# LED_CUBE_595.net
KiCad netlist of a schematic drawn in EAGLE
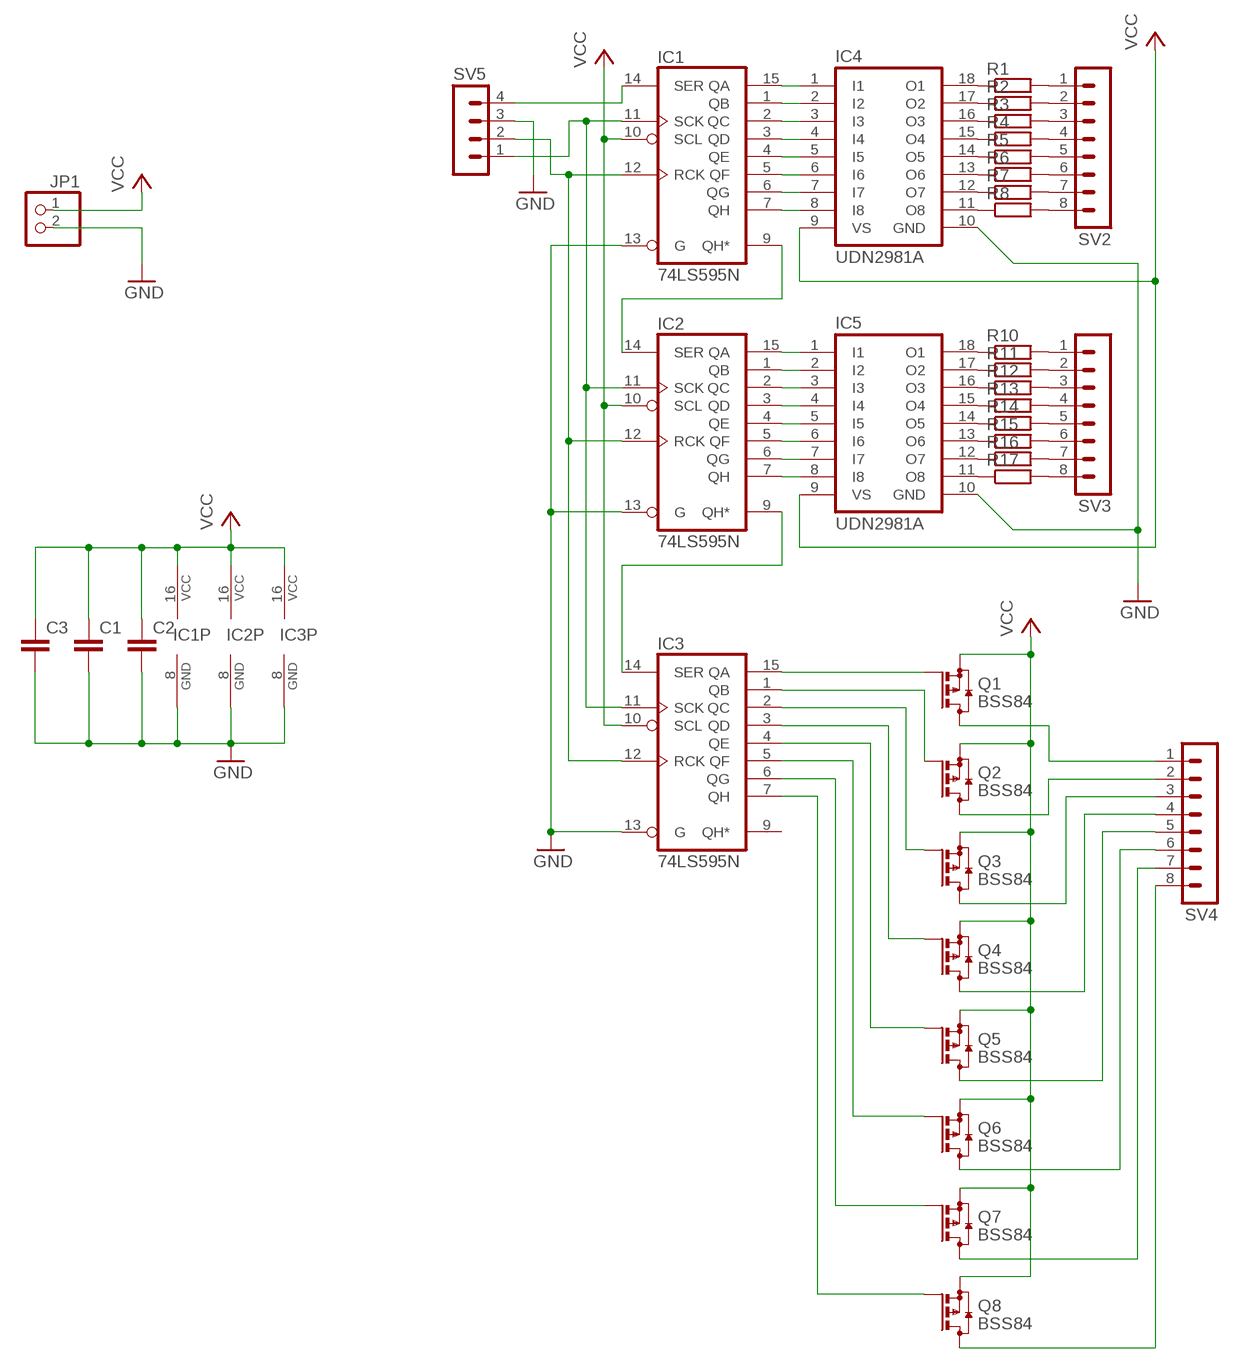
[diagram p0: schematic, sheet 1]

(export (version "E")
  (design (tool "Eeschema 10.0.6"))
  (components
    (comp (ref "C1")
      (value "C-EU025-025X050")
      (footprint "eagle-import:C025-025X050")
      (libsource (lib "eagle-import") (part "C-EU025-025X050"))
    )
    (comp (ref "C2")
      (value "C-EU025-025X050")
      (footprint "eagle-import:C025-025X050")
      (libsource (lib "eagle-import") (part "C-EU025-025X050"))
    )
    (comp (ref "C3")
      (value "C-EU025-025X050")
      (footprint "eagle-import:C025-025X050")
      (libsource (lib "eagle-import") (part "C-EU025-025X050"))
    )
    (comp (ref "IC1")
      (value "74LS595N")
      (footprint "eagle-import:DIL16")
      (libsource (lib "eagle-import") (part "74595NLS"))
    )
    (comp (ref "IC2")
      (value "74LS595N")
      (footprint "eagle-import:DIL16")
      (libsource (lib "eagle-import") (part "74595NLS"))
    )
    (comp (ref "IC3")
      (value "74LS595N")
      (footprint "eagle-import:DIL16")
      (libsource (lib "eagle-import") (part "74595NLS"))
    )
    (comp (ref "IC4")
      (value "UDN2981A")
      (footprint "eagle-import:DIL18")
      (libsource (lib "eagle-import") (part "UDN298A1"))
    )
    (comp (ref "IC5")
      (value "UDN2981A")
      (footprint "eagle-import:DIL18")
      (libsource (lib "eagle-import") (part "UDN298A1"))
    )
    (comp (ref "JP1")
      (value "PINHD-1X2")
      (footprint "eagle-import:1X02")
      (libsource (lib "eagle-import") (part "PINHD-1X2"))
    )
    (comp (ref "Q1")
      (value "BSS84")
      (footprint "eagle-import:SOT23")
      (libsource (lib "eagle-import") (part "BSS84"))
    )
    (comp (ref "Q2")
      (value "BSS84")
      (footprint "eagle-import:SOT23")
      (libsource (lib "eagle-import") (part "BSS84"))
    )
    (comp (ref "Q3")
      (value "BSS84")
      (footprint "eagle-import:SOT23")
      (libsource (lib "eagle-import") (part "BSS84"))
    )
    (comp (ref "Q4")
      (value "BSS84")
      (footprint "eagle-import:SOT23")
      (libsource (lib "eagle-import") (part "BSS84"))
    )
    (comp (ref "Q5")
      (value "BSS84")
      (footprint "eagle-import:SOT23")
      (libsource (lib "eagle-import") (part "BSS84"))
    )
    (comp (ref "Q6")
      (value "BSS84")
      (footprint "eagle-import:SOT23")
      (libsource (lib "eagle-import") (part "BSS84"))
    )
    (comp (ref "Q7")
      (value "BSS84")
      (footprint "eagle-import:SOT23")
      (libsource (lib "eagle-import") (part "BSS84"))
    )
    (comp (ref "Q8")
      (value "BSS84")
      (footprint "eagle-import:SOT23")
      (libsource (lib "eagle-import") (part "BSS84"))
    )
    (comp (ref "R1")
      (value "R-EU_0204/2V")
      (footprint "eagle-import:0204V")
      (libsource (lib "eagle-import") (part "R-EU_0204/2V"))
    )
    (comp (ref "R2")
      (value "R-EU_0204/2V")
      (footprint "eagle-import:0204V")
      (libsource (lib "eagle-import") (part "R-EU_0204/2V"))
    )
    (comp (ref "R3")
      (value "R-EU_0204/2V")
      (footprint "eagle-import:0204V")
      (libsource (lib "eagle-import") (part "R-EU_0204/2V"))
    )
    (comp (ref "R4")
      (value "R-EU_0204/2V")
      (footprint "eagle-import:0204V")
      (libsource (lib "eagle-import") (part "R-EU_0204/2V"))
    )
    (comp (ref "R5")
      (value "R-EU_0204/2V")
      (footprint "eagle-import:0204V")
      (libsource (lib "eagle-import") (part "R-EU_0204/2V"))
    )
    (comp (ref "R6")
      (value "R-EU_0204/2V")
      (footprint "eagle-import:0204V")
      (libsource (lib "eagle-import") (part "R-EU_0204/2V"))
    )
    (comp (ref "R7")
      (value "R-EU_0204/2V")
      (footprint "eagle-import:0204V")
      (libsource (lib "eagle-import") (part "R-EU_0204/2V"))
    )
    (comp (ref "R8")
      (value "R-EU_0204/2V")
      (footprint "eagle-import:0204V")
      (libsource (lib "eagle-import") (part "R-EU_0204/2V"))
    )
    (comp (ref "R10")
      (value "R-EU_0204/2V")
      (footprint "eagle-import:0204V")
      (libsource (lib "eagle-import") (part "R-EU_0204/2V"))
    )
    (comp (ref "R11")
      (value "R-EU_0204/2V")
      (footprint "eagle-import:0204V")
      (libsource (lib "eagle-import") (part "R-EU_0204/2V"))
    )
    (comp (ref "R12")
      (value "R-EU_0204/2V")
      (footprint "eagle-import:0204V")
      (libsource (lib "eagle-import") (part "R-EU_0204/2V"))
    )
    (comp (ref "R13")
      (value "R-EU_0204/2V")
      (footprint "eagle-import:0204V")
      (libsource (lib "eagle-import") (part "R-EU_0204/2V"))
    )
    (comp (ref "R14")
      (value "R-EU_0204/2V")
      (footprint "eagle-import:0204V")
      (libsource (lib "eagle-import") (part "R-EU_0204/2V"))
    )
    (comp (ref "R15")
      (value "R-EU_0204/2V")
      (footprint "eagle-import:0204V")
      (libsource (lib "eagle-import") (part "R-EU_0204/2V"))
    )
    (comp (ref "R16")
      (value "R-EU_0204/2V")
      (footprint "eagle-import:0204V")
      (libsource (lib "eagle-import") (part "R-EU_0204/2V"))
    )
    (comp (ref "R17")
      (value "R-EU_0204/2V")
      (footprint "eagle-import:0204V")
      (libsource (lib "eagle-import") (part "R-EU_0204/2V"))
    )
    (comp (ref "SV2")
      (value "MA08-1")
      (footprint "eagle-import:MA08-1")
      (libsource (lib "eagle-import") (part "MA08-1"))
    )
    (comp (ref "SV3")
      (value "MA08-1")
      (footprint "eagle-import:MA08-1")
      (libsource (lib "eagle-import") (part "MA08-1"))
    )
    (comp (ref "SV4")
      (value "MA08-1")
      (footprint "eagle-import:MA08-1")
      (libsource (lib "eagle-import") (part "MA08-1"))
    )
    (comp (ref "SV5")
      (value "MA04-1")
      (footprint "eagle-import:MA04-1")
      (libsource (lib "eagle-import") (part "MA04-1"))
    )
  )
  (nets
    (net (code "1") (name "GND") (class "Default")
      (node (ref "C1") (pin "2") (pinfunction "2_2") (pintype "passive"))
      (node (ref "C2") (pin "2") (pinfunction "2_2") (pintype "passive"))
      (node (ref "C3") (pin "2") (pinfunction "2_2") (pintype "passive"))
      (node (ref "IC1") (pin "13") (pinfunction "G_13") (pintype "input"))
      (node (ref "IC1") (pin "8") (pinfunction "GND_8") (pintype "power_in"))
      (node (ref "IC2") (pin "13") (pinfunction "G_13") (pintype "input"))
      (node (ref "IC2") (pin "8") (pinfunction "GND_8") (pintype "power_in"))
      (node (ref "IC3") (pin "13") (pinfunction "G_13") (pintype "input"))
      (node (ref "IC3") (pin "8") (pinfunction "GND_8") (pintype "power_in"))
      (node (ref "IC4") (pin "10") (pinfunction "GND_10") (pintype "power_in"))
      (node (ref "IC5") (pin "10") (pinfunction "GND_10") (pintype "power_in"))
      (node (ref "JP1") (pin "2") (pinfunction "2_2") (pintype "passive"))
      (node (ref "SV5") (pin "3") (pinfunction "3_3") (pintype "passive"))
    )
    (net (code "2") (name "Net-(IC1A-QA)") (class "Default")
      (node (ref "IC1") (pin "15") (pinfunction "QA_15") (pintype "tri_state"))
      (node (ref "IC4") (pin "1") (pinfunction "I1_1") (pintype "input"))
    )
    (net (code "3") (name "Net-(IC1A-QB)") (class "Default")
      (node (ref "IC1") (pin "1") (pinfunction "QB_1") (pintype "tri_state"))
      (node (ref "IC4") (pin "2") (pinfunction "I2_2") (pintype "input"))
    )
    (net (code "4") (name "Net-(IC1A-QC)") (class "Default")
      (node (ref "IC1") (pin "2") (pinfunction "QC_2") (pintype "tri_state"))
      (node (ref "IC4") (pin "3") (pinfunction "I3_3") (pintype "input"))
    )
    (net (code "5") (name "Net-(IC1A-QD)") (class "Default")
      (node (ref "IC1") (pin "3") (pinfunction "QD_3") (pintype "tri_state"))
      (node (ref "IC4") (pin "4") (pinfunction "I4_4") (pintype "input"))
    )
    (net (code "6") (name "Net-(IC1A-QE)") (class "Default")
      (node (ref "IC1") (pin "4") (pinfunction "QE_4") (pintype "tri_state"))
      (node (ref "IC4") (pin "5") (pinfunction "I5_5") (pintype "input"))
    )
    (net (code "7") (name "Net-(IC1A-QF)") (class "Default")
      (node (ref "IC1") (pin "5") (pinfunction "QF_5") (pintype "tri_state"))
      (node (ref "IC4") (pin "6") (pinfunction "I6_6") (pintype "input"))
    )
    (net (code "8") (name "Net-(IC1A-QG)") (class "Default")
      (node (ref "IC1") (pin "6") (pinfunction "QG_6") (pintype "tri_state"))
      (node (ref "IC4") (pin "7") (pinfunction "I7_7") (pintype "input"))
    )
    (net (code "9") (name "Net-(IC1A-QH)") (class "Default")
      (node (ref "IC1") (pin "7") (pinfunction "QH_7") (pintype "tri_state"))
      (node (ref "IC4") (pin "8") (pinfunction "I8_8") (pintype "input"))
    )
    (net (code "10") (name "Net-(IC1A-QH*)") (class "Default")
      (node (ref "IC1") (pin "9") (pinfunction "QH*_9") (pintype "tri_state"))
      (node (ref "IC2") (pin "14") (pinfunction "SER_14") (pintype "input"))
    )
    (net (code "11") (name "Net-(IC1A-RCK)") (class "Default")
      (node (ref "IC1") (pin "12") (pinfunction "RCK_12") (pintype "input"))
      (node (ref "IC2") (pin "12") (pinfunction "RCK_12") (pintype "input"))
      (node (ref "IC3") (pin "12") (pinfunction "RCK_12") (pintype "input"))
      (node (ref "SV5") (pin "2") (pinfunction "2_2") (pintype "passive"))
    )
    (net (code "12") (name "Net-(IC1A-SCK)") (class "Default")
      (node (ref "IC1") (pin "11") (pinfunction "SCK_11") (pintype "input"))
      (node (ref "IC2") (pin "11") (pinfunction "SCK_11") (pintype "input"))
      (node (ref "IC3") (pin "11") (pinfunction "SCK_11") (pintype "input"))
      (node (ref "SV5") (pin "1") (pinfunction "1_1") (pintype "passive"))
    )
    (net (code "13") (name "Net-(IC1A-SER)") (class "Default")
      (node (ref "IC1") (pin "14") (pinfunction "SER_14") (pintype "input"))
      (node (ref "SV5") (pin "4") (pinfunction "4_4") (pintype "passive"))
    )
    (net (code "14") (name "Net-(IC2A-QA)") (class "Default")
      (node (ref "IC2") (pin "15") (pinfunction "QA_15") (pintype "tri_state"))
      (node (ref "IC5") (pin "1") (pinfunction "I1_1") (pintype "input"))
    )
    (net (code "15") (name "Net-(IC2A-QB)") (class "Default")
      (node (ref "IC2") (pin "1") (pinfunction "QB_1") (pintype "tri_state"))
      (node (ref "IC5") (pin "2") (pinfunction "I2_2") (pintype "input"))
    )
    (net (code "16") (name "Net-(IC2A-QC)") (class "Default")
      (node (ref "IC2") (pin "2") (pinfunction "QC_2") (pintype "tri_state"))
      (node (ref "IC5") (pin "3") (pinfunction "I3_3") (pintype "input"))
    )
    (net (code "17") (name "Net-(IC2A-QD)") (class "Default")
      (node (ref "IC2") (pin "3") (pinfunction "QD_3") (pintype "tri_state"))
      (node (ref "IC5") (pin "4") (pinfunction "I4_4") (pintype "input"))
    )
    (net (code "18") (name "Net-(IC2A-QE)") (class "Default")
      (node (ref "IC2") (pin "4") (pinfunction "QE_4") (pintype "tri_state"))
      (node (ref "IC5") (pin "5") (pinfunction "I5_5") (pintype "input"))
    )
    (net (code "19") (name "Net-(IC2A-QF)") (class "Default")
      (node (ref "IC2") (pin "5") (pinfunction "QF_5") (pintype "tri_state"))
      (node (ref "IC5") (pin "6") (pinfunction "I6_6") (pintype "input"))
    )
    (net (code "20") (name "Net-(IC2A-QG)") (class "Default")
      (node (ref "IC2") (pin "6") (pinfunction "QG_6") (pintype "tri_state"))
      (node (ref "IC5") (pin "7") (pinfunction "I7_7") (pintype "input"))
    )
    (net (code "21") (name "Net-(IC2A-QH)") (class "Default")
      (node (ref "IC2") (pin "7") (pinfunction "QH_7") (pintype "tri_state"))
      (node (ref "IC5") (pin "8") (pinfunction "I8_8") (pintype "input"))
    )
    (net (code "22") (name "Net-(IC2A-QH*)") (class "Default")
      (node (ref "IC2") (pin "9") (pinfunction "QH*_9") (pintype "tri_state"))
      (node (ref "IC3") (pin "14") (pinfunction "SER_14") (pintype "input"))
    )
    (net (code "23") (name "Net-(IC3A-QA)") (class "Default")
      (node (ref "IC3") (pin "15") (pinfunction "QA_15") (pintype "tri_state"))
      (node (ref "Q1") (pin "1") (pinfunction "G_1") (pintype "passive"))
    )
    (net (code "24") (name "Net-(IC3A-QB)") (class "Default")
      (node (ref "IC3") (pin "1") (pinfunction "QB_1") (pintype "tri_state"))
      (node (ref "Q2") (pin "1") (pinfunction "G_1") (pintype "passive"))
    )
    (net (code "25") (name "Net-(IC3A-QC)") (class "Default")
      (node (ref "IC3") (pin "2") (pinfunction "QC_2") (pintype "tri_state"))
      (node (ref "Q3") (pin "1") (pinfunction "G_1") (pintype "passive"))
    )
    (net (code "26") (name "Net-(IC3A-QD)") (class "Default")
      (node (ref "IC3") (pin "3") (pinfunction "QD_3") (pintype "tri_state"))
      (node (ref "Q4") (pin "1") (pinfunction "G_1") (pintype "passive"))
    )
    (net (code "27") (name "Net-(IC3A-QE)") (class "Default")
      (node (ref "IC3") (pin "4") (pinfunction "QE_4") (pintype "tri_state"))
      (node (ref "Q5") (pin "1") (pinfunction "G_1") (pintype "passive"))
    )
    (net (code "28") (name "Net-(IC3A-QF)") (class "Default")
      (node (ref "IC3") (pin "5") (pinfunction "QF_5") (pintype "tri_state"))
      (node (ref "Q6") (pin "1") (pinfunction "G_1") (pintype "passive"))
    )
    (net (code "29") (name "Net-(IC3A-QG)") (class "Default")
      (node (ref "IC3") (pin "6") (pinfunction "QG_6") (pintype "tri_state"))
      (node (ref "Q7") (pin "1") (pinfunction "G_1") (pintype "passive"))
    )
    (net (code "30") (name "Net-(IC3A-QH)") (class "Default")
      (node (ref "IC3") (pin "7") (pinfunction "QH_7") (pintype "tri_state"))
      (node (ref "Q8") (pin "1") (pinfunction "G_1") (pintype "passive"))
    )
    (net (code "31") (name "Net-(IC4-O1)") (class "Default")
      (node (ref "IC4") (pin "18") (pinfunction "O1_18") (pintype "open_collector"))
      (node (ref "R1") (pin "1") (pinfunction "1_1") (pintype "passive"))
    )
    (net (code "32") (name "Net-(IC4-O2)") (class "Default")
      (node (ref "IC4") (pin "17") (pinfunction "O2_17") (pintype "open_collector"))
      (node (ref "R2") (pin "1") (pinfunction "1_1") (pintype "passive"))
    )
    (net (code "33") (name "Net-(IC4-O3)") (class "Default")
      (node (ref "IC4") (pin "16") (pinfunction "O3_16") (pintype "open_collector"))
      (node (ref "R3") (pin "1") (pinfunction "1_1") (pintype "passive"))
    )
    (net (code "34") (name "Net-(IC4-O4)") (class "Default")
      (node (ref "IC4") (pin "15") (pinfunction "O4_15") (pintype "open_collector"))
      (node (ref "R4") (pin "1") (pinfunction "1_1") (pintype "passive"))
    )
    (net (code "35") (name "Net-(IC4-O5)") (class "Default")
      (node (ref "IC4") (pin "14") (pinfunction "O5_14") (pintype "open_collector"))
      (node (ref "R5") (pin "1") (pinfunction "1_1") (pintype "passive"))
    )
    (net (code "36") (name "Net-(IC4-O6)") (class "Default")
      (node (ref "IC4") (pin "13") (pinfunction "O6_13") (pintype "open_collector"))
      (node (ref "R6") (pin "1") (pinfunction "1_1") (pintype "passive"))
    )
    (net (code "37") (name "Net-(IC4-O7)") (class "Default")
      (node (ref "IC4") (pin "12") (pinfunction "O7_12") (pintype "open_collector"))
      (node (ref "R7") (pin "1") (pinfunction "1_1") (pintype "passive"))
    )
    (net (code "38") (name "Net-(IC4-O8)") (class "Default")
      (node (ref "IC4") (pin "11") (pinfunction "O8_11") (pintype "open_collector"))
      (node (ref "R8") (pin "1") (pinfunction "1_1") (pintype "passive"))
    )
    (net (code "39") (name "Net-(IC5-O1)") (class "Default")
      (node (ref "IC5") (pin "18") (pinfunction "O1_18") (pintype "open_collector"))
      (node (ref "R10") (pin "1") (pinfunction "1_1") (pintype "passive"))
    )
    (net (code "40") (name "Net-(IC5-O2)") (class "Default")
      (node (ref "IC5") (pin "17") (pinfunction "O2_17") (pintype "open_collector"))
      (node (ref "R11") (pin "1") (pinfunction "1_1") (pintype "passive"))
    )
    (net (code "41") (name "Net-(IC5-O3)") (class "Default")
      (node (ref "IC5") (pin "16") (pinfunction "O3_16") (pintype "open_collector"))
      (node (ref "R12") (pin "1") (pinfunction "1_1") (pintype "passive"))
    )
    (net (code "42") (name "Net-(IC5-O4)") (class "Default")
      (node (ref "IC5") (pin "15") (pinfunction "O4_15") (pintype "open_collector"))
      (node (ref "R13") (pin "1") (pinfunction "1_1") (pintype "passive"))
    )
    (net (code "43") (name "Net-(IC5-O5)") (class "Default")
      (node (ref "IC5") (pin "14") (pinfunction "O5_14") (pintype "open_collector"))
      (node (ref "R14") (pin "1") (pinfunction "1_1") (pintype "passive"))
    )
    (net (code "44") (name "Net-(IC5-O6)") (class "Default")
      (node (ref "IC5") (pin "13") (pinfunction "O6_13") (pintype "open_collector"))
      (node (ref "R15") (pin "1") (pinfunction "1_1") (pintype "passive"))
    )
    (net (code "45") (name "Net-(IC5-O7)") (class "Default")
      (node (ref "IC5") (pin "12") (pinfunction "O7_12") (pintype "open_collector"))
      (node (ref "R16") (pin "1") (pinfunction "1_1") (pintype "passive"))
    )
    (net (code "46") (name "Net-(IC5-O8)") (class "Default")
      (node (ref "IC5") (pin "11") (pinfunction "O8_11") (pintype "open_collector"))
      (node (ref "R17") (pin "1") (pinfunction "1_1") (pintype "passive"))
    )
    (net (code "47") (name "Net-(Q1-D)") (class "Default")
      (node (ref "Q1") (pin "3") (pinfunction "D_3") (pintype "passive"))
      (node (ref "SV4") (pin "1") (pinfunction "1_1") (pintype "passive"))
    )
    (net (code "48") (name "Net-(Q2-D)") (class "Default")
      (node (ref "Q2") (pin "3") (pinfunction "D_3") (pintype "passive"))
      (node (ref "SV4") (pin "2") (pinfunction "2_2") (pintype "passive"))
    )
    (net (code "49") (name "Net-(Q3-D)") (class "Default")
      (node (ref "Q3") (pin "3") (pinfunction "D_3") (pintype "passive"))
      (node (ref "SV4") (pin "3") (pinfunction "3_3") (pintype "passive"))
    )
    (net (code "50") (name "Net-(Q4-D)") (class "Default")
      (node (ref "Q4") (pin "3") (pinfunction "D_3") (pintype "passive"))
      (node (ref "SV4") (pin "4") (pinfunction "4_4") (pintype "passive"))
    )
    (net (code "51") (name "Net-(Q5-D)") (class "Default")
      (node (ref "Q5") (pin "3") (pinfunction "D_3") (pintype "passive"))
      (node (ref "SV4") (pin "5") (pinfunction "5_5") (pintype "passive"))
    )
    (net (code "52") (name "Net-(Q6-D)") (class "Default")
      (node (ref "Q6") (pin "3") (pinfunction "D_3") (pintype "passive"))
      (node (ref "SV4") (pin "6") (pinfunction "6_6") (pintype "passive"))
    )
    (net (code "53") (name "Net-(Q7-D)") (class "Default")
      (node (ref "Q7") (pin "3") (pinfunction "D_3") (pintype "passive"))
      (node (ref "SV4") (pin "7") (pinfunction "7_7") (pintype "passive"))
    )
    (net (code "54") (name "Net-(Q8-D)") (class "Default")
      (node (ref "Q8") (pin "3") (pinfunction "D_3") (pintype "passive"))
      (node (ref "SV4") (pin "8") (pinfunction "8_8") (pintype "passive"))
    )
    (net (code "55") (name "Net-(R1-Pad2)") (class "Default")
      (node (ref "R1") (pin "2") (pinfunction "2_2") (pintype "passive"))
      (node (ref "SV2") (pin "1") (pinfunction "1_1") (pintype "passive"))
    )
    (net (code "56") (name "Net-(R2-Pad2)") (class "Default")
      (node (ref "R2") (pin "2") (pinfunction "2_2") (pintype "passive"))
      (node (ref "SV2") (pin "2") (pinfunction "2_2") (pintype "passive"))
    )
    (net (code "57") (name "Net-(R3-Pad2)") (class "Default")
      (node (ref "R3") (pin "2") (pinfunction "2_2") (pintype "passive"))
      (node (ref "SV2") (pin "3") (pinfunction "3_3") (pintype "passive"))
    )
    (net (code "58") (name "Net-(R4-Pad2)") (class "Default")
      (node (ref "R4") (pin "2") (pinfunction "2_2") (pintype "passive"))
      (node (ref "SV2") (pin "4") (pinfunction "4_4") (pintype "passive"))
    )
    (net (code "59") (name "Net-(R5-Pad2)") (class "Default")
      (node (ref "R5") (pin "2") (pinfunction "2_2") (pintype "passive"))
      (node (ref "SV2") (pin "5") (pinfunction "5_5") (pintype "passive"))
    )
    (net (code "60") (name "Net-(R6-Pad2)") (class "Default")
      (node (ref "R6") (pin "2") (pinfunction "2_2") (pintype "passive"))
      (node (ref "SV2") (pin "6") (pinfunction "6_6") (pintype "passive"))
    )
    (net (code "61") (name "Net-(R7-Pad2)") (class "Default")
      (node (ref "R7") (pin "2") (pinfunction "2_2") (pintype "passive"))
      (node (ref "SV2") (pin "7") (pinfunction "7_7") (pintype "passive"))
    )
    (net (code "62") (name "Net-(R8-Pad2)") (class "Default")
      (node (ref "R8") (pin "2") (pinfunction "2_2") (pintype "passive"))
      (node (ref "SV2") (pin "8") (pinfunction "8_8") (pintype "passive"))
    )
    (net (code "63") (name "Net-(R10-Pad2)") (class "Default")
      (node (ref "R10") (pin "2") (pinfunction "2_2") (pintype "passive"))
      (node (ref "SV3") (pin "1") (pinfunction "1_1") (pintype "passive"))
    )
    (net (code "64") (name "Net-(R11-Pad2)") (class "Default")
      (node (ref "R11") (pin "2") (pinfunction "2_2") (pintype "passive"))
      (node (ref "SV3") (pin "2") (pinfunction "2_2") (pintype "passive"))
    )
    (net (code "65") (name "Net-(R12-Pad2)") (class "Default")
      (node (ref "R12") (pin "2") (pinfunction "2_2") (pintype "passive"))
      (node (ref "SV3") (pin "3") (pinfunction "3_3") (pintype "passive"))
    )
    (net (code "66") (name "Net-(R13-Pad2)") (class "Default")
      (node (ref "R13") (pin "2") (pinfunction "2_2") (pintype "passive"))
      (node (ref "SV3") (pin "4") (pinfunction "4_4") (pintype "passive"))
    )
    (net (code "67") (name "Net-(R14-Pad2)") (class "Default")
      (node (ref "R14") (pin "2") (pinfunction "2_2") (pintype "passive"))
      (node (ref "SV3") (pin "5") (pinfunction "5_5") (pintype "passive"))
    )
    (net (code "68") (name "Net-(R15-Pad2)") (class "Default")
      (node (ref "R15") (pin "2") (pinfunction "2_2") (pintype "passive"))
      (node (ref "SV3") (pin "6") (pinfunction "6_6") (pintype "passive"))
    )
    (net (code "69") (name "Net-(R16-Pad2)") (class "Default")
      (node (ref "R16") (pin "2") (pinfunction "2_2") (pintype "passive"))
      (node (ref "SV3") (pin "7") (pinfunction "7_7") (pintype "passive"))
    )
    (net (code "70") (name "Net-(R17-Pad2)") (class "Default")
      (node (ref "R17") (pin "2") (pinfunction "2_2") (pintype "passive"))
      (node (ref "SV3") (pin "8") (pinfunction "8_8") (pintype "passive"))
    )
    (net (code "71") (name "VCC") (class "Default")
      (node (ref "C1") (pin "1") (pinfunction "1_1") (pintype "passive"))
      (node (ref "C2") (pin "1") (pinfunction "1_1") (pintype "passive"))
      (node (ref "C3") (pin "1") (pinfunction "1_1") (pintype "passive"))
      (node (ref "IC1") (pin "10") (pinfunction "SCL_10") (pintype "input"))
      (node (ref "IC1") (pin "16") (pinfunction "VCC_16") (pintype "power_in"))
      (node (ref "IC2") (pin "10") (pinfunction "SCL_10") (pintype "input"))
      (node (ref "IC2") (pin "16") (pinfunction "VCC_16") (pintype "power_in"))
      (node (ref "IC3") (pin "10") (pinfunction "SCL_10") (pintype "input"))
      (node (ref "IC3") (pin "16") (pinfunction "VCC_16") (pintype "power_in"))
      (node (ref "IC4") (pin "9") (pinfunction "VS_9") (pintype "passive"))
      (node (ref "IC5") (pin "9") (pinfunction "VS_9") (pintype "passive"))
      (node (ref "JP1") (pin "1") (pinfunction "1_1") (pintype "passive"))
      (node (ref "Q1") (pin "2") (pinfunction "S_2") (pintype "passive"))
      (node (ref "Q2") (pin "2") (pinfunction "S_2") (pintype "passive"))
      (node (ref "Q3") (pin "2") (pinfunction "S_2") (pintype "passive"))
      (node (ref "Q4") (pin "2") (pinfunction "S_2") (pintype "passive"))
      (node (ref "Q5") (pin "2") (pinfunction "S_2") (pintype "passive"))
      (node (ref "Q6") (pin "2") (pinfunction "S_2") (pintype "passive"))
      (node (ref "Q7") (pin "2") (pinfunction "S_2") (pintype "passive"))
      (node (ref "Q8") (pin "2") (pinfunction "S_2") (pintype "passive"))
    )
    (net (code "72") (name "unconnected-(IC3A-QH*-Pad9)") (class "Default")
      (node (ref "IC3") (pin "9") (pinfunction "QH*_9") (pintype "tri_state"))
    )
  )
)
